# Microcontroller_STC12C5A60S2.net
KiCad netlist of a schematic drawn in Altium Designer
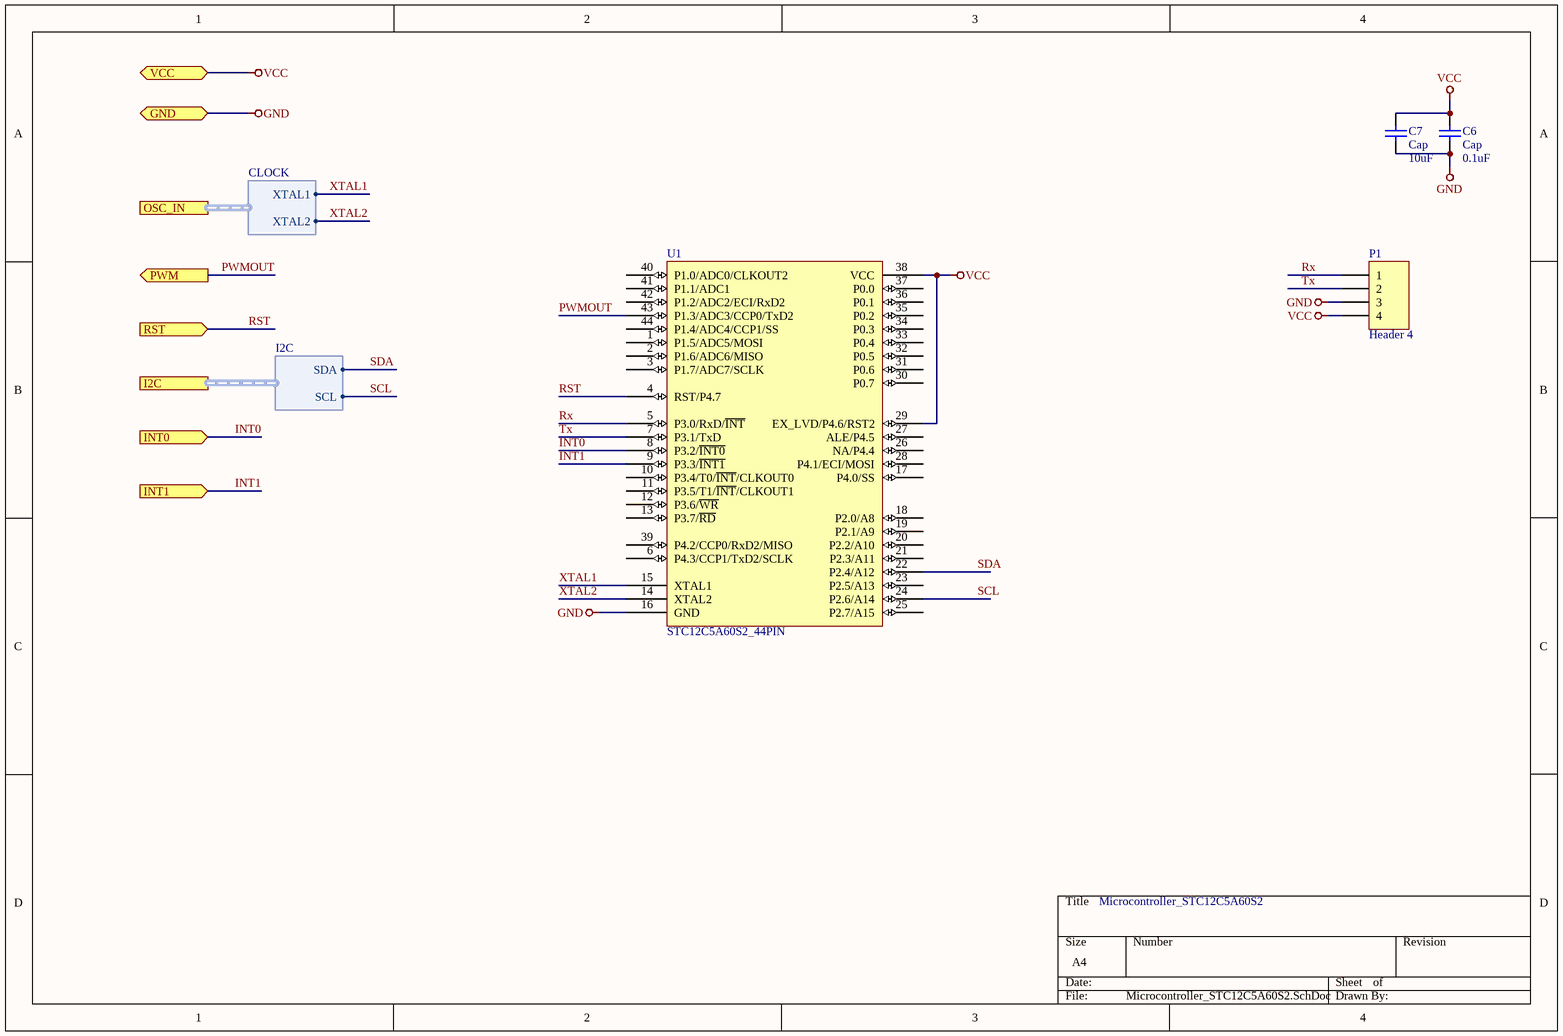
[diagram p0: Microcontroller_STC12C5A60S2.SchDoc]

(export (version "E")
  (design (tool "Eeschema 10.0.6"))
  (components
    (comp (ref "C6")
      (value "Cap")
      (footprint "C0805")
      (description "Non-Polar Capacitor")
      (fields (field (name "ALTIUM_VALUE") "0.1uF"))
      (libsource (lib "Integrated_Library") (part "Cap"))
    )
    (comp (ref "C7")
      (value "Cap")
      (footprint "1206C")
      (description "Non-Polar Capacitor")
      (fields (field (name "ALTIUM_VALUE") "10uF"))
      (libsource (lib "Integrated_Library") (part "Cap"))
    )
    (comp (ref "P1")
      (value "Header 4")
      (footprint "HDR1X4HA")
      (description "Header, 4-Pin")
      (fields (field (name "PUBLISHER") "Altium Limited"))
      (libsource (lib "Schlib") (part "Header 4"))
    )
    (comp (ref "U1")
      (value "STC12C5A60S2_44PIN")
      (footprint "STC12C5A60S2_44PIN")
      (description "MCU")
      (libsource (lib "Integrated_Library") (part "STC12C5A60S2_44PIN"))
    )
  )
  (nets
    (net (code "3") (name "/INT0") (class "Default")
      (node (ref "U1") (pin "8") (pinfunction "P3.2/~{INT0}_8") (pintype "bidirectional"))
    )
    (net (code "4") (name "/INT1") (class "Default")
      (node (ref "U1") (pin "9") (pinfunction "P3.3/~{INT1}_9") (pintype "bidirectional"))
    )
    (net (code "5") (name "/PWMOUT") (class "Default")
      (node (ref "U1") (pin "43") (pinfunction "P1.3/ADC3/CCP0/TxD2_43") (pintype "bidirectional"))
    )
    (net (code "6") (name "/RST") (class "Default")
      (node (ref "U1") (pin "4") (pinfunction "RST/P4.7_4") (pintype "bidirectional"))
    )
    (net (code "7") (name "/Rx") (class "Default")
      (node (ref "P1") (pin "1") (pinfunction "1_1") (pintype "passive"))
      (node (ref "U1") (pin "5") (pinfunction "P3.0/RxD/~{INT}_5") (pintype "bidirectional"))
    )
    (net (code "8") (name "/SCL") (class "Default")
      (node (ref "U1") (pin "24") (pinfunction "P2.6/A14_24") (pintype "bidirectional"))
    )
    (net (code "9") (name "/SDA") (class "Default")
      (node (ref "U1") (pin "22") (pinfunction "P2.4/A12_22") (pintype "bidirectional"))
    )
    (net (code "10") (name "/Tx") (class "Default")
      (node (ref "P1") (pin "2") (pinfunction "2_2") (pintype "passive"))
      (node (ref "U1") (pin "7") (pinfunction "P3.1/TxD_7") (pintype "bidirectional"))
    )
    (net (code "11") (name "/XTAL1") (class "Default")
      (node (ref "U1") (pin "15") (pinfunction "XTAL1_15") (pintype "passive"))
    )
    (net (code "12") (name "/XTAL2") (class "Default")
      (node (ref "U1") (pin "14") (pinfunction "XTAL2_14") (pintype "passive"))
    )
    (net (code "15") (name "GND") (class "Default")
      (node (ref "C6") (pin "1") (pinfunction "1_1") (pintype "passive"))
      (node (ref "C7") (pin "1") (pinfunction "1_1") (pintype "passive"))
      (node (ref "P1") (pin "3") (pinfunction "3_3") (pintype "passive"))
      (node (ref "U1") (pin "16") (pinfunction "GND_16") (pintype "power_in"))
    )
    (net (code "16") (name "VCC") (class "Default")
      (node (ref "C6") (pin "2") (pinfunction "2_2") (pintype "passive"))
      (node (ref "C7") (pin "2") (pinfunction "2_2") (pintype "passive"))
      (node (ref "P1") (pin "4") (pinfunction "4_4") (pintype "passive"))
      (node (ref "U1") (pin "29") (pinfunction "EX_LVD/P4.6/RST2_29") (pintype "bidirectional"))
      (node (ref "U1") (pin "38") (pinfunction "VCC_38") (pintype "power_in"))
    )
    (net (code "17") (name "unconnected-(U1-ALE{slash}P4.5-Pad27)") (class "Default")
      (node (ref "U1") (pin "27") (pinfunction "ALE/P4.5_27") (pintype "bidirectional"))
    )
    (net (code "18") (name "unconnected-(U1-NA{slash}P4.4-Pad26)") (class "Default")
      (node (ref "U1") (pin "26") (pinfunction "NA/P4.4_26") (pintype "bidirectional"))
    )
    (net (code "19") (name "unconnected-(U1-P0.0-Pad37)") (class "Default")
      (node (ref "U1") (pin "37") (pinfunction "P0.0_37") (pintype "bidirectional"))
    )
    (net (code "20") (name "unconnected-(U1-P0.1-Pad36)") (class "Default")
      (node (ref "U1") (pin "36") (pinfunction "P0.1_36") (pintype "bidirectional"))
    )
    (net (code "21") (name "unconnected-(U1-P0.2-Pad35)") (class "Default")
      (node (ref "U1") (pin "35") (pinfunction "P0.2_35") (pintype "bidirectional"))
    )
    (net (code "22") (name "unconnected-(U1-P0.3-Pad34)") (class "Default")
      (node (ref "U1") (pin "34") (pinfunction "P0.3_34") (pintype "bidirectional"))
    )
    (net (code "23") (name "unconnected-(U1-P0.4-Pad33)") (class "Default")
      (node (ref "U1") (pin "33") (pinfunction "P0.4_33") (pintype "bidirectional"))
    )
    (net (code "24") (name "unconnected-(U1-P0.5-Pad32)") (class "Default")
      (node (ref "U1") (pin "32") (pinfunction "P0.5_32") (pintype "bidirectional"))
    )
    (net (code "25") (name "unconnected-(U1-P0.6-Pad31)") (class "Default")
      (node (ref "U1") (pin "31") (pinfunction "P0.6_31") (pintype "bidirectional"))
    )
    (net (code "26") (name "unconnected-(U1-P0.7-Pad30)") (class "Default")
      (node (ref "U1") (pin "30") (pinfunction "P0.7_30") (pintype "bidirectional"))
    )
    (net (code "27") (name "unconnected-(U1-P1.0{slash}ADC0{slash}CLKOUT2-Pad40)") (class "Default")
      (node (ref "U1") (pin "40") (pinfunction "P1.0/ADC0/CLKOUT2_40") (pintype "bidirectional"))
    )
    (net (code "28") (name "unconnected-(U1-P1.1{slash}ADC1-Pad41)") (class "Default")
      (node (ref "U1") (pin "41") (pinfunction "P1.1/ADC1_41") (pintype "bidirectional"))
    )
    (net (code "29") (name "unconnected-(U1-P1.2{slash}ADC2{slash}ECI{slash}RxD2-Pad42)") (class "Default")
      (node (ref "U1") (pin "42") (pinfunction "P1.2/ADC2/ECI/RxD2_42") (pintype "bidirectional"))
    )
    (net (code "30") (name "unconnected-(U1-P1.4{slash}ADC4{slash}CCP1{slash}SS-Pad44)") (class "Default")
      (node (ref "U1") (pin "44") (pinfunction "P1.4/ADC4/CCP1/SS_44") (pintype "bidirectional"))
    )
    (net (code "31") (name "unconnected-(U1-P1.5{slash}ADC5{slash}MOSI-Pad1)") (class "Default")
      (node (ref "U1") (pin "1") (pinfunction "P1.5/ADC5/MOSI_1") (pintype "bidirectional"))
    )
    (net (code "32") (name "unconnected-(U1-P1.6{slash}ADC6{slash}MISO-Pad2)") (class "Default")
      (node (ref "U1") (pin "2") (pinfunction "P1.6/ADC6/MISO_2") (pintype "bidirectional"))
    )
    (net (code "33") (name "unconnected-(U1-P1.7{slash}ADC7{slash}SCLK-Pad3)") (class "Default")
      (node (ref "U1") (pin "3") (pinfunction "P1.7/ADC7/SCLK_3") (pintype "bidirectional"))
    )
    (net (code "34") (name "unconnected-(U1-P2.0{slash}A8-Pad18)") (class "Default")
      (node (ref "U1") (pin "18") (pinfunction "P2.0/A8_18") (pintype "bidirectional"))
    )
    (net (code "35") (name "unconnected-(U1-P2.1{slash}A9-Pad19)") (class "Default")
      (node (ref "U1") (pin "19") (pinfunction "P2.1/A9_19") (pintype "bidirectional"))
    )
    (net (code "36") (name "unconnected-(U1-P2.2{slash}A10-Pad20)") (class "Default")
      (node (ref "U1") (pin "20") (pinfunction "P2.2/A10_20") (pintype "bidirectional"))
    )
    (net (code "37") (name "unconnected-(U1-P2.3{slash}A11-Pad21)") (class "Default")
      (node (ref "U1") (pin "21") (pinfunction "P2.3/A11_21") (pintype "bidirectional"))
    )
    (net (code "38") (name "unconnected-(U1-P2.5{slash}A13-Pad23)") (class "Default")
      (node (ref "U1") (pin "23") (pinfunction "P2.5/A13_23") (pintype "bidirectional"))
    )
    (net (code "39") (name "unconnected-(U1-P2.7{slash}A15-Pad25)") (class "Default")
      (node (ref "U1") (pin "25") (pinfunction "P2.7/A15_25") (pintype "bidirectional"))
    )
    (net (code "40") (name "unconnected-(U1-P3.4{slash}T0{slash}~{INT}{slash}CLKOUT0-Pad10)") (class "Default")
      (node (ref "U1") (pin "10") (pinfunction "P3.4/T0/~{INT}/CLKOUT0_10") (pintype "bidirectional"))
    )
    (net (code "41") (name "unconnected-(U1-P3.5{slash}T1{slash}~{INT}{slash}CLKOUT1-Pad11)") (class "Default")
      (node (ref "U1") (pin "11") (pinfunction "P3.5/T1/~{INT}/CLKOUT1_11") (pintype "bidirectional"))
    )
    (net (code "42") (name "unconnected-(U1-P3.6{slash}~{WR}-Pad12)") (class "Default")
      (node (ref "U1") (pin "12") (pinfunction "P3.6/~{WR}_12") (pintype "bidirectional"))
    )
    (net (code "43") (name "unconnected-(U1-P3.7{slash}~{RD}-Pad13)") (class "Default")
      (node (ref "U1") (pin "13") (pinfunction "P3.7/~{RD}_13") (pintype "bidirectional"))
    )
    (net (code "44") (name "unconnected-(U1-P4.0{slash}SS-Pad17)") (class "Default")
      (node (ref "U1") (pin "17") (pinfunction "P4.0/SS_17") (pintype "bidirectional"))
    )
    (net (code "45") (name "unconnected-(U1-P4.1{slash}ECI{slash}MOSI-Pad28)") (class "Default")
      (node (ref "U1") (pin "28") (pinfunction "P4.1/ECI/MOSI_28") (pintype "bidirectional"))
    )
    (net (code "46") (name "unconnected-(U1-P4.2{slash}CCP0{slash}RxD2{slash}MISO-Pad39)") (class "Default")
      (node (ref "U1") (pin "39") (pinfunction "P4.2/CCP0/RxD2/MISO_39") (pintype "bidirectional"))
    )
    (net (code "47") (name "unconnected-(U1-P4.3{slash}CCP1{slash}TxD2{slash}SCLK-Pad6)") (class "Default")
      (node (ref "U1") (pin "6") (pinfunction "P4.3/CCP1/TxD2/SCLK_6") (pintype "bidirectional"))
    )
  )
)
